# power.net
KiCad netlist of a schematic drawn in Altium Designer
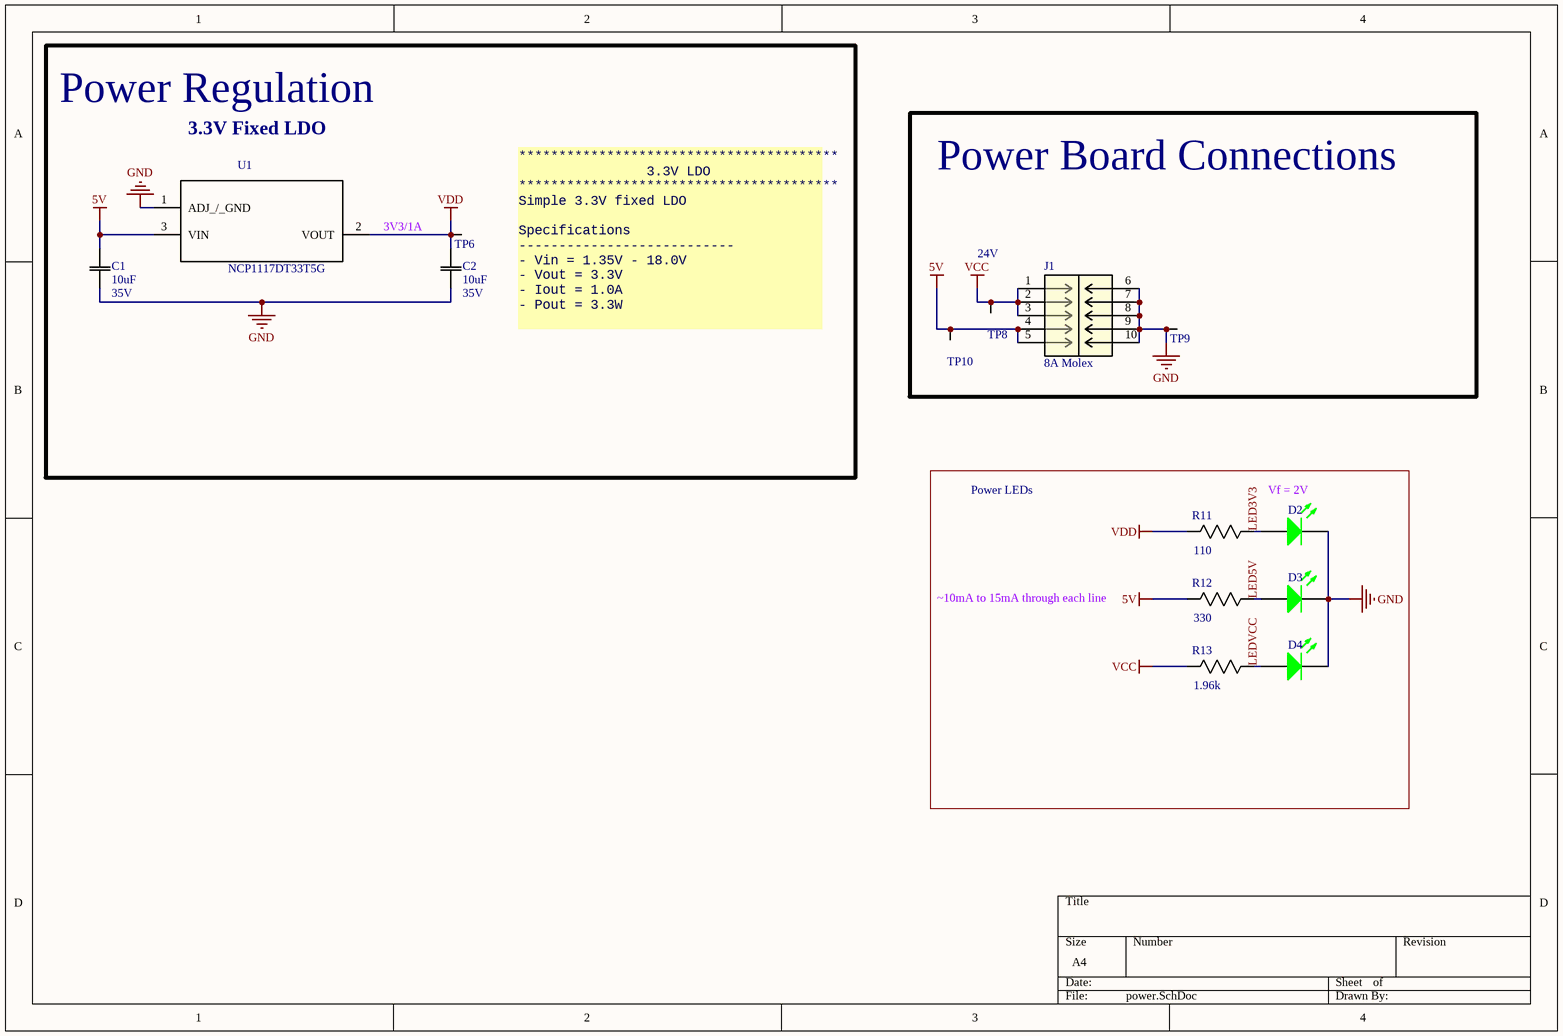
[diagram p0: power.SchDoc]

(export (version "E")
  (design (tool "Eeschema 10.0.6"))
  (components
    (comp (ref "C1")
      (value "10uF")
      (footprint "0805")
      (description "Default Symbol for Capacitors")
      (fields
        (field (name "TOLERANCE") "10%")
        (field (name "RATING") "35V")
        (field (name "PART NUMBER") "CAP 10uF 35V_1")
      )
      (libsource (lib "capacitor_library") (part "CAP_Default"))
    )
    (comp (ref "C2")
      (value "10uF")
      (footprint "0805")
      (description "Default Symbol for Capacitors")
      (fields
        (field (name "TOLERANCE") "10%")
        (field (name "RATING") "35V")
        (field (name "PART NUMBER") "CAP 10uF 35V_1")
      )
      (libsource (lib "capacitor_library") (part "CAP_Default"))
    )
    (comp (ref "D2")
      (value "0603 2V")
      (footprint "0603 - LED")
      (description "LED Uni-Color Green 574nm 2-Pin Chip LED T/R")
      (fields (field (name "PART NUMBER") "LED GREEN SMD 0603"))
      (libsource (lib "Diode_Library") (part "LED GREEN SMD 0603"))
    )
    (comp (ref "D3")
      (value "0603 2V")
      (footprint "0603 - LED")
      (description "LED Uni-Color Green 574nm 2-Pin Chip LED T/R")
      (fields (field (name "PART NUMBER") "LED GREEN SMD 0603"))
      (libsource (lib "Diode_Library") (part "LED GREEN SMD 0603"))
    )
    (comp (ref "D4")
      (value "0603 2V")
      (footprint "0603 - LED")
      (description "LED Uni-Color Green 574nm 2-Pin Chip LED T/R")
      (fields (field (name "PART NUMBER") "LED GREEN SMD 0603"))
      (libsource (lib "Diode_Library") (part "LED GREEN SMD 0603"))
    )
    (comp (ref "J1")
      (value "8A Molex")
      (footprint "MOLEX_0430451012")
      (description "CONN HEADER VERT 10POS 3MM")
      (fields (field (name "PART NUMBER") "CN HDR 10POS MOLEX 0430451012"))
      (libsource (lib "Connector_Library") (part "CN HDR 10POS MOLEX 0430451012"))
    )
    (comp (ref "R11")
      (value "110")
      (footprint "0603")
      (description "Default Resistor Symbol")
      (fields (field (name "TOLERANCE") "1%") (field (name "PART NUMBER") "RES 110.0 1/8W - 1%"))
      (libsource (lib "Resistor_Library") (part "RES_DEFAULT"))
    )
    (comp (ref "R12")
      (value "330")
      (footprint "0603")
      (description "Default Resistor Symbol")
      (fields (field (name "TOLERANCE") "5%") (field (name "PART NUMBER") "RES 330.0 1/8W - 5%"))
      (libsource (lib "") (part "RES_DEFAULT_1"))
    )
    (comp (ref "R13")
      (value "1.96k")
      (footprint "0603")
      (description "Default Resistor Symbol")
      (fields (field (name "TOLERANCE") "1%") (field (name "PART NUMBER") "RES 1.96k 1/8W"))
      (libsource (lib "") (part "RES_DEFAULT_1"))
    )
    (comp (ref "TP6")
      (value "VDD")
      (footprint "TP")
      (fields (field (name "PART NUMBER") "Test Point (Via)"))
      (libsource (lib "IC_Library") (part "Test Point (Via)"))
    )
    (comp (ref "TP8")
      (value "VCC")
      (footprint "TP")
      (fields (field (name "PART NUMBER") "Test Point (Via)"))
      (libsource (lib "IC_Library") (part "Test Point (Via)"))
    )
    (comp (ref "TP9")
      (value "GND")
      (footprint "TP")
      (fields (field (name "PART NUMBER") "Test Point (Via)"))
      (libsource (lib "IC_Library") (part "Test Point (Via)"))
    )
    (comp (ref "TP10")
      (value "5V")
      (footprint "TP")
      (fields (field (name "PART NUMBER") "Test Point (Via)"))
      (libsource (lib "IC_Library") (part "Test Point (Via)"))
    )
    (comp (ref "U1")
      (value "NCP1117DT33T5G")
      (footprint "DPAK (TO-252)")
      (description "Linear Voltage Regulator IC Positive Fixed 1 Output 1A DPAK")
      (libsource (lib "IC_Library") (part "NCP1117DT33T5G"))
    )
  )
  (nets
    (net (code "1") (name "/LED3V3") (class "Default")
      (node (ref "D2") (pin "1") (pinfunction "A_1") (pintype "passive"))
      (node (ref "R11") (pin "1") (pinfunction "R1_1") (pintype "passive"))
    )
    (net (code "2") (name "/LED5V") (class "Default")
      (node (ref "D3") (pin "1") (pinfunction "A_1") (pintype "passive"))
      (node (ref "R12") (pin "1") (pinfunction "R1_1") (pintype "passive"))
    )
    (net (code "3") (name "/LEDVCC") (class "Default")
      (node (ref "D4") (pin "1") (pinfunction "A_1") (pintype "passive"))
      (node (ref "R13") (pin "1") (pinfunction "R1_1") (pintype "passive"))
    )
    (net (code "4") (name "5V") (class "Default")
      (node (ref "C1") (pin "2") (pinfunction "C2_2") (pintype "passive"))
      (node (ref "J1") (pin "4") (pinfunction "4_4") (pintype "passive"))
      (node (ref "J1") (pin "5") (pinfunction "5_5") (pintype "passive"))
      (node (ref "R12") (pin "2") (pinfunction "R2_2") (pintype "passive"))
      (node (ref "TP10") (pin "1") (pinfunction "1_1") (pintype "passive"))
      (node (ref "U1") (pin "3") (pinfunction "VIN_3") (pintype "power_in"))
    )
    (net (code "5") (name "GND") (class "Default")
      (node (ref "C1") (pin "1") (pinfunction "C1_1") (pintype "passive"))
      (node (ref "C2") (pin "1") (pinfunction "C1_1") (pintype "passive"))
      (node (ref "D2") (pin "2") (pinfunction "K_2") (pintype "passive"))
      (node (ref "D3") (pin "2") (pinfunction "K_2") (pintype "passive"))
      (node (ref "D4") (pin "2") (pinfunction "K_2") (pintype "passive"))
      (node (ref "J1") (pin "10") (pinfunction "10_10") (pintype "passive"))
      (node (ref "J1") (pin "6") (pinfunction "6_6") (pintype "passive"))
      (node (ref "J1") (pin "7") (pinfunction "7_7") (pintype "passive"))
      (node (ref "J1") (pin "8") (pinfunction "8_8") (pintype "passive"))
      (node (ref "J1") (pin "9") (pinfunction "9_9") (pintype "passive"))
      (node (ref "TP9") (pin "1") (pinfunction "1_1") (pintype "passive"))
      (node (ref "U1") (pin "1") (pinfunction "ADJ_/_GND_1") (pintype "power_in"))
    )
    (net (code "6") (name "VCC") (class "Default")
      (node (ref "J1") (pin "1") (pinfunction "1_1") (pintype "passive"))
      (node (ref "J1") (pin "2") (pinfunction "2_2") (pintype "passive"))
      (node (ref "J1") (pin "3") (pinfunction "3_3") (pintype "passive"))
      (node (ref "R13") (pin "2") (pinfunction "R2_2") (pintype "passive"))
      (node (ref "TP8") (pin "1") (pinfunction "1_1") (pintype "passive"))
    )
    (net (code "7") (name "VDD") (class "Default")
      (node (ref "C2") (pin "2") (pinfunction "C2_2") (pintype "passive"))
      (node (ref "R11") (pin "2") (pinfunction "R2_2") (pintype "passive"))
      (node (ref "TP6") (pin "1") (pinfunction "1_1") (pintype "passive"))
      (node (ref "U1") (pin "2") (pinfunction "VOUT_2") (pintype "power_in"))
    )
  )
)
